# Input_amplifiers.net
KiCad netlist of a schematic drawn in Altium Designer
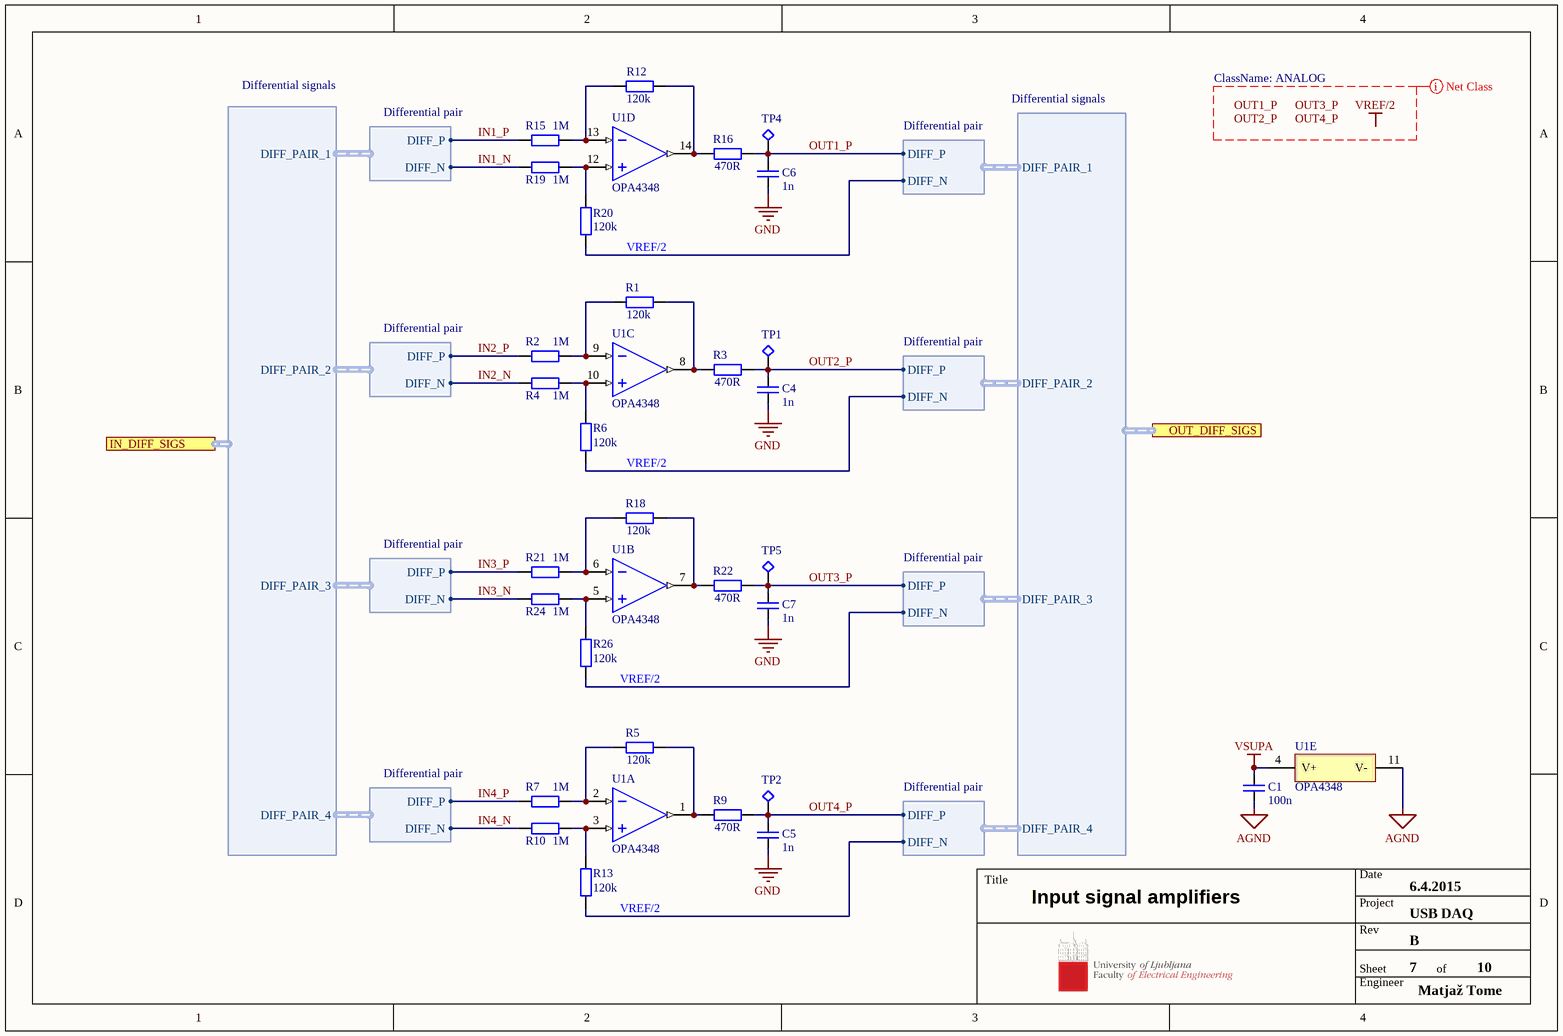
[diagram p0: Input_amplifiers.SchDoc]

(export (version "E")
  (design (tool "Eeschema 10.0.6"))
  (components
    (comp (ref "C1")
      (value "100n")
      (footprint "C_0603")
      (description "Generic capacitor")
      (fields (field (name "Comment") "comment"))
      (libsource (lib "DAQ") (part "Capacitor"))
    )
    (comp (ref "C4")
      (value "1n")
      (footprint "C_0603")
      (description "Generic capacitor")
      (fields (field (name "Comment") "comment"))
      (libsource (lib "DAQ") (part "Capacitor"))
    )
    (comp (ref "C5")
      (value "1n")
      (footprint "C_0603")
      (description "Generic capacitor")
      (fields (field (name "Comment") "comment"))
      (libsource (lib "DAQ") (part "Capacitor"))
    )
    (comp (ref "C6")
      (value "1n")
      (footprint "C_0603")
      (description "Generic capacitor")
      (fields (field (name "Comment") "comment"))
      (libsource (lib "DAQ") (part "Capacitor"))
    )
    (comp (ref "C7")
      (value "1n")
      (footprint "C_0603")
      (description "Generic capacitor")
      (fields (field (name "Comment") "comment"))
      (libsource (lib "DAQ") (part "Capacitor"))
    )
    (comp (ref "R1")
      (value "120k")
      (footprint "R_0603")
      (description "Generic resistor")
      (fields (field (name "Comment") "comment"))
      (libsource (lib "DAQ") (part "Resistor"))
    )
    (comp (ref "R2")
      (value "1M")
      (footprint "R_0603")
      (description "Generic resistor")
      (fields (field (name "Comment") "comment"))
      (libsource (lib "DAQ") (part "Resistor"))
    )
    (comp (ref "R3")
      (value "470R")
      (footprint "R_0603")
      (description "Generic resistor")
      (fields (field (name "Comment") "comment"))
      (libsource (lib "DAQ") (part "Resistor"))
    )
    (comp (ref "R4")
      (value "1M")
      (footprint "R_0603")
      (description "Generic resistor")
      (fields (field (name "Comment") "comment"))
      (libsource (lib "DAQ") (part "Resistor"))
    )
    (comp (ref "R5")
      (value "120k")
      (footprint "R_0603")
      (description "Generic resistor")
      (fields (field (name "Comment") "comment"))
      (libsource (lib "DAQ") (part "Resistor"))
    )
    (comp (ref "R6")
      (value "120k")
      (footprint "R_0603")
      (description "Generic resistor")
      (fields (field (name "Comment") "comment"))
      (libsource (lib "DAQ") (part "Resistor"))
    )
    (comp (ref "R7")
      (value "1M")
      (footprint "R_0603")
      (description "Generic resistor")
      (fields (field (name "Comment") "comment"))
      (libsource (lib "DAQ") (part "Resistor"))
    )
    (comp (ref "R9")
      (value "470R")
      (footprint "R_0603")
      (description "Generic resistor")
      (fields (field (name "Comment") "comment"))
      (libsource (lib "DAQ") (part "Resistor"))
    )
    (comp (ref "R10")
      (value "1M")
      (footprint "R_0603")
      (description "Generic resistor")
      (fields (field (name "Comment") "comment"))
      (libsource (lib "DAQ") (part "Resistor"))
    )
    (comp (ref "R12")
      (value "120k")
      (footprint "R_0603")
      (description "Generic resistor")
      (fields (field (name "Comment") "comment"))
      (libsource (lib "DAQ") (part "Resistor"))
    )
    (comp (ref "R13")
      (value "120k")
      (footprint "R_0603")
      (description "Generic resistor")
      (fields (field (name "Comment") "comment"))
      (libsource (lib "DAQ") (part "Resistor"))
    )
    (comp (ref "R15")
      (value "1M")
      (footprint "R_0603")
      (description "Generic resistor")
      (fields (field (name "Comment") "comment"))
      (libsource (lib "DAQ") (part "Resistor"))
    )
    (comp (ref "R16")
      (value "470R")
      (footprint "R_0603")
      (description "Generic resistor")
      (fields (field (name "Comment") "comment"))
      (libsource (lib "DAQ") (part "Resistor"))
    )
    (comp (ref "R18")
      (value "120k")
      (footprint "R_0603")
      (description "Generic resistor")
      (fields (field (name "Comment") "comment"))
      (libsource (lib "DAQ") (part "Resistor"))
    )
    (comp (ref "R19")
      (value "1M")
      (footprint "R_0603")
      (description "Generic resistor")
      (fields (field (name "Comment") "comment"))
      (libsource (lib "DAQ") (part "Resistor"))
    )
    (comp (ref "R20")
      (value "120k")
      (footprint "R_0603")
      (description "Generic resistor")
      (fields (field (name "Comment") "comment"))
      (libsource (lib "DAQ") (part "Resistor"))
    )
    (comp (ref "R21")
      (value "1M")
      (footprint "R_0603")
      (description "Generic resistor")
      (fields (field (name "Comment") "comment"))
      (libsource (lib "DAQ") (part "Resistor"))
    )
    (comp (ref "R22")
      (value "470R")
      (footprint "R_0603")
      (description "Generic resistor")
      (fields (field (name "Comment") "comment"))
      (libsource (lib "DAQ") (part "Resistor"))
    )
    (comp (ref "R24")
      (value "1M")
      (footprint "R_0603")
      (description "Generic resistor")
      (fields (field (name "Comment") "comment"))
      (libsource (lib "DAQ") (part "Resistor"))
    )
    (comp (ref "R26")
      (value "120k")
      (footprint "R_0603")
      (description "Generic resistor")
      (fields (field (name "Comment") "comment"))
      (libsource (lib "DAQ") (part "Resistor"))
    )
    (comp (ref "TP1")
      (value "testpoint")
      (footprint "TP1_FULL")
      (description "testpoint 1.5mm diameter no hole")
      (fields (field (name "PART NUMBER") "XXC0006"))
      (libsource (lib "DAQ") (part "Test Point"))
    )
    (comp (ref "TP2")
      (value "testpoint")
      (footprint "TP1_FULL")
      (description "testpoint 1.5mm diameter no hole")
      (fields (field (name "PART NUMBER") "XXC0006"))
      (libsource (lib "DAQ") (part "Test Point"))
    )
    (comp (ref "TP4")
      (value "testpoint")
      (footprint "TP1_FULL")
      (description "testpoint 1.5mm diameter no hole")
      (fields (field (name "PART NUMBER") "XXC0006"))
      (libsource (lib "DAQ") (part "Test Point"))
    )
    (comp (ref "TP5")
      (value "testpoint")
      (footprint "TP1_FULL")
      (description "testpoint 1.5mm diameter no hole")
      (fields (field (name "PART NUMBER") "XXC0006"))
      (libsource (lib "DAQ") (part "Test Point"))
    )
    (comp (ref "U1")
      (value "OPA4348")
      (footprint "SOIC14")
      (description "1MHz, 45µA, CMOS, Rail-to-Rail OPERATIONAL AMPLIFIERS Value Line Series")
      (fields (field (name "PART NUMBER") "XOG0008") (field (name "MANUFACTURER") "Texas Instruments"))
      (libsource (lib "DAQ") (part "OPA4348"))
    )
  )
  (nets
    (net (code "8") (name "/IN1_N") (class "Default") (node (ref "R19") (pin "1") (pintype "passive")))
    (net (code "9") (name "/IN1_P") (class "Default") (node (ref "R15") (pin "1") (pintype "passive")))
    (net (code "10") (name "/IN2_N") (class "Default") (node (ref "R4") (pin "1") (pintype "passive")))
    (net (code "11") (name "/IN2_P") (class "Default") (node (ref "R2") (pin "1") (pintype "passive")))
    (net (code "12") (name "/IN3_N") (class "Default") (node (ref "R24") (pin "1") (pintype "passive")))
    (net (code "13") (name "/IN3_P") (class "Default") (node (ref "R21") (pin "1") (pintype "passive")))
    (net (code "14") (name "/IN4_N") (class "Default") (node (ref "R10") (pin "1") (pintype "passive")))
    (net (code "15") (name "/IN4_P") (class "Default") (node (ref "R7") (pin "1") (pintype "passive")))
    (net (code "17") (name "/OUT1_P") (class "Default")
      (node (ref "C6") (pin "1") (pinfunction "1_1") (pintype "passive"))
      (node (ref "R16") (pin "2") (pintype "passive"))
      (node (ref "TP4") (pin "1") (pinfunction "1_1") (pintype "passive"))
    )
    (net (code "18") (name "/OUT2_P") (class "Default")
      (node (ref "C4") (pin "1") (pinfunction "1_1") (pintype "passive"))
      (node (ref "R3") (pin "2") (pintype "passive"))
      (node (ref "TP1") (pin "1") (pinfunction "1_1") (pintype "passive"))
    )
    (net (code "19") (name "/OUT3_P") (class "Default")
      (node (ref "C7") (pin "1") (pinfunction "1_1") (pintype "passive"))
      (node (ref "R22") (pin "2") (pintype "passive"))
      (node (ref "TP5") (pin "1") (pinfunction "1_1") (pintype "passive"))
    )
    (net (code "20") (name "/OUT4_P") (class "Default")
      (node (ref "C5") (pin "1") (pinfunction "1_1") (pintype "passive"))
      (node (ref "R9") (pin "2") (pintype "passive"))
      (node (ref "TP2") (pin "1") (pinfunction "1_1") (pintype "passive"))
    )
    (net (code "24") (name "AGND") (class "Default")
      (node (ref "C1") (pin "1") (pinfunction "1_1") (pintype "passive"))
      (node (ref "U1") (pin "11") (pinfunction "V-_11") (pintype "power_in"))
    )
    (net (code "25") (name "GND") (class "Default")
      (node (ref "C4") (pin "2") (pinfunction "2_2") (pintype "passive"))
      (node (ref "C5") (pin "2") (pinfunction "2_2") (pintype "passive"))
      (node (ref "C6") (pin "2") (pinfunction "2_2") (pintype "passive"))
      (node (ref "C7") (pin "2") (pinfunction "2_2") (pintype "passive"))
    )
    (net (code "26") (name "Net-(U1A-+IN_A)") (class "Default")
      (node (ref "R10") (pin "2") (pintype "passive"))
      (node (ref "R13") (pin "2") (pintype "passive"))
      (node (ref "U1") (pin "3") (pinfunction "+IN_A_3") (pintype "input"))
    )
    (net (code "27") (name "Net-(U1A--IN_A)") (class "Default")
      (node (ref "R5") (pin "1") (pintype "passive"))
      (node (ref "R7") (pin "2") (pintype "passive"))
      (node (ref "U1") (pin "2") (pinfunction "-IN_A_2") (pintype "input"))
    )
    (net (code "28") (name "Net-(U1A-OUT_A)") (class "Default")
      (node (ref "R5") (pin "2") (pintype "passive"))
      (node (ref "R9") (pin "1") (pintype "passive"))
      (node (ref "U1") (pin "1") (pinfunction "OUT_A_1") (pintype "output"))
    )
    (net (code "29") (name "Net-(U1B-+IN_B)") (class "Default")
      (node (ref "R24") (pin "2") (pintype "passive"))
      (node (ref "R26") (pin "2") (pintype "passive"))
      (node (ref "U1") (pin "5") (pinfunction "+IN_B_5") (pintype "input"))
    )
    (net (code "30") (name "Net-(U1B--IN_B)") (class "Default")
      (node (ref "R18") (pin "1") (pintype "passive"))
      (node (ref "R21") (pin "2") (pintype "passive"))
      (node (ref "U1") (pin "6") (pinfunction "-IN_B_6") (pintype "input"))
    )
    (net (code "31") (name "Net-(U1B-OUT_B)") (class "Default")
      (node (ref "R18") (pin "2") (pintype "passive"))
      (node (ref "R22") (pin "1") (pintype "passive"))
      (node (ref "U1") (pin "7") (pinfunction "OUT_B_7") (pintype "output"))
    )
    (net (code "32") (name "Net-(U1C-+IN_C)") (class "Default")
      (node (ref "R4") (pin "2") (pintype "passive"))
      (node (ref "R6") (pin "2") (pintype "passive"))
      (node (ref "U1") (pin "10") (pinfunction "+IN_C_10") (pintype "input"))
    )
    (net (code "33") (name "Net-(U1C--IN_C)") (class "Default")
      (node (ref "R1") (pin "1") (pintype "passive"))
      (node (ref "R2") (pin "2") (pintype "passive"))
      (node (ref "U1") (pin "9") (pinfunction "-IN_C_9") (pintype "input"))
    )
    (net (code "34") (name "Net-(U1C-OUT_C)") (class "Default")
      (node (ref "R1") (pin "2") (pintype "passive"))
      (node (ref "R3") (pin "1") (pintype "passive"))
      (node (ref "U1") (pin "8") (pinfunction "OUT_C_8") (pintype "output"))
    )
    (net (code "35") (name "Net-(U1D-+IN_D)") (class "Default")
      (node (ref "R19") (pin "2") (pintype "passive"))
      (node (ref "R20") (pin "2") (pintype "passive"))
      (node (ref "U1") (pin "12") (pinfunction "+IN_D_12") (pintype "input"))
    )
    (net (code "36") (name "Net-(U1D--IN_D)") (class "Default")
      (node (ref "R12") (pin "1") (pintype "passive"))
      (node (ref "R15") (pin "2") (pintype "passive"))
      (node (ref "U1") (pin "13") (pinfunction "-IN_D_13") (pintype "input"))
    )
    (net (code "37") (name "Net-(U1D-OUT_D)") (class "Default")
      (node (ref "R12") (pin "2") (pintype "passive"))
      (node (ref "R16") (pin "1") (pintype "passive"))
      (node (ref "U1") (pin "14") (pinfunction "OUT_D_14") (pintype "output"))
    )
    (net (code "39") (name "VSUPA") (class "Default")
      (node (ref "C1") (pin "2") (pinfunction "2_2") (pintype "passive"))
      (node (ref "U1") (pin "4") (pinfunction "V+_4") (pintype "power_in"))
    )
    (net (code "40") (name "unconnected-(R6-Pad1)") (class "Default")
      (node (ref "R6") (pin "1") (pintype "passive"))
    )
    (net (code "41") (name "unconnected-(R13-Pad1)") (class "Default")
      (node (ref "R13") (pin "1") (pintype "passive"))
    )
    (net (code "42") (name "unconnected-(R20-Pad1)") (class "Default")
      (node (ref "R20") (pin "1") (pintype "passive"))
    )
    (net (code "43") (name "unconnected-(R26-Pad1)") (class "Default")
      (node (ref "R26") (pin "1") (pintype "passive"))
    )
  )
)
